# EFM32_IO.net
KiCad netlist of a schematic drawn in Altium Designer
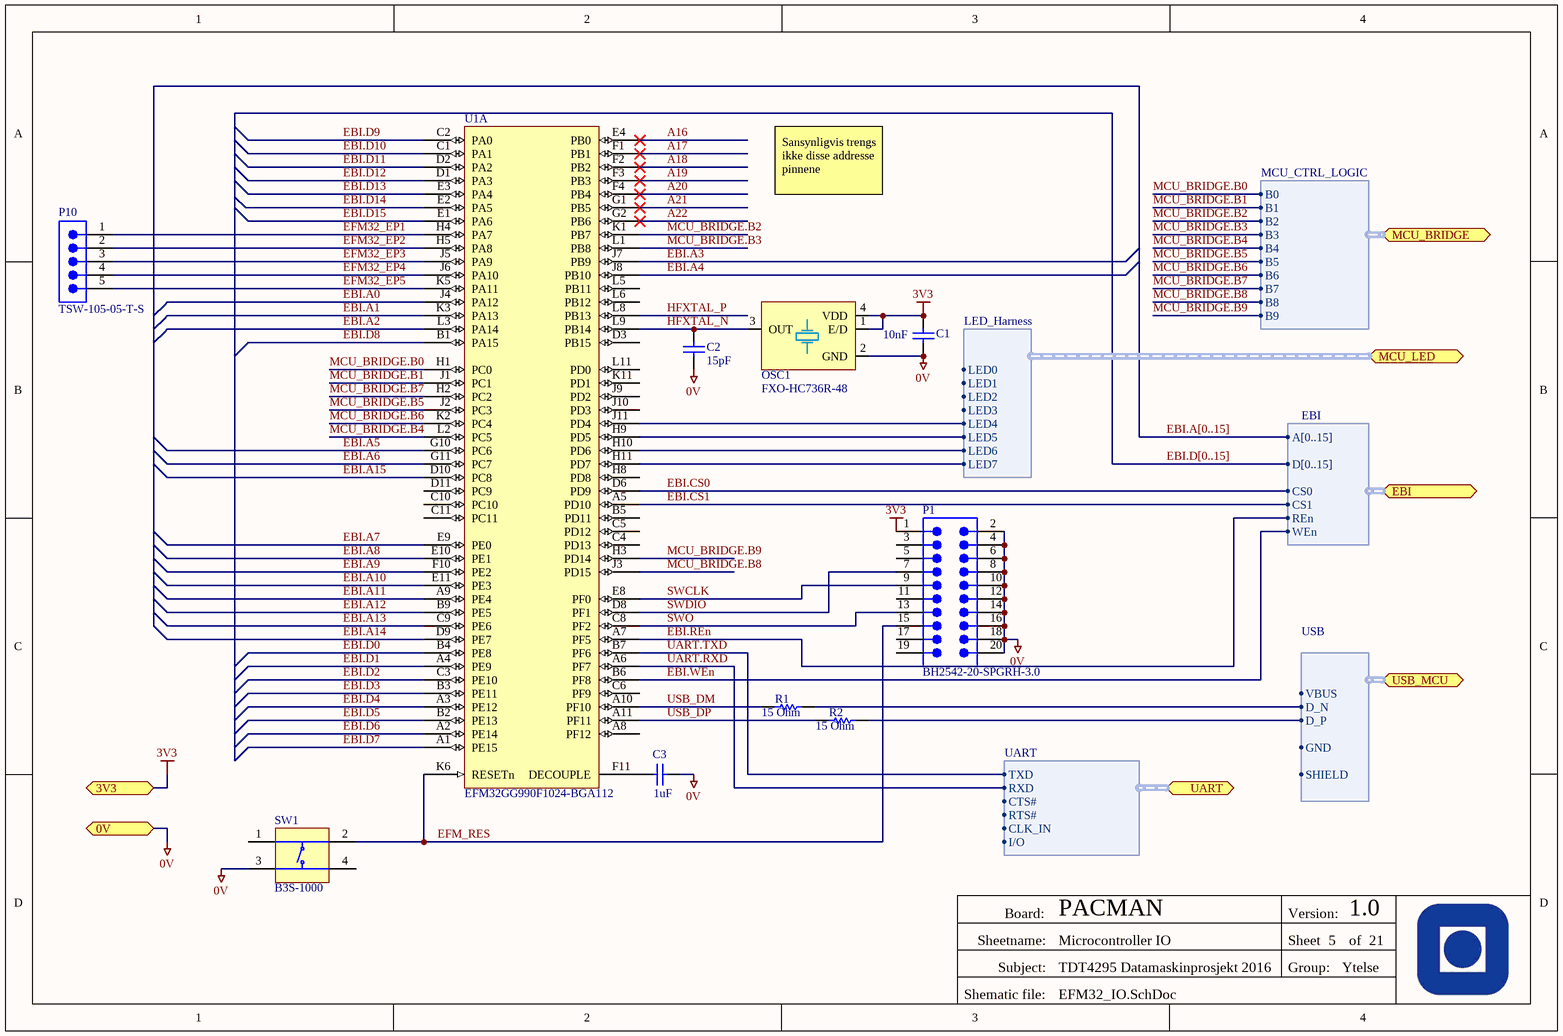
[diagram p0: EFM32_IO.SchDoc]

(export (version "E")
  (design (tool "Eeschema 10.0.6"))
  (components
    (comp (ref "C1")
      (value "10nF")
      (footprint "CAPC0603(1608)100_L")
      (description "CAP 10nF 16V ±1% 0603 (1608 Metric) Thickness 1mm SMD")
      (fields (field (name "TOLERANCE") "Â±1%") (field (name "Comment") "CAP 10nF 16V 0603(1608)"))
      (libsource (lib "Altium Content Vault") (part "CMP-1035-02309-1"))
    )
    (comp (ref "C2")
      (value "15pF")
      (footprint "CAPC0603(1608)100_N")
      (description "CAP 15pF 16V ±0.25pF 0603 (1608 Metric) Thickness 1mm SMD")
      (fields (field (name "TOLERANCE") "Â±0.25pF") (field (name "Comment") "CAP 15pF 16V 0603(1608)"))
      (libsource (lib "Altium Content Vault") (part "CMP-1035-00665-1"))
    )
    (comp (ref "C3")
      (value "1uF")
      (footprint "CAPC0603(1608)100_M")
      (description "CAP 1uF 16V ±10% 0603 (1608 Metric) Thickness 1mm SMD")
      (fields (field (name "TOLERANCE") "Â±10%") (field (name "Comment") "CAP 1uF 16V 0603(1608)"))
      (libsource (lib "Altium Content Vault") (part "CMP-1035-02737-1"))
    )
    (comp (ref "OSC1")
      (value "FXO-HC736R-48")
      (footprint "FXO-HC73")
      (libsource (lib "dmpro16lib") (part "FXO-HC736R-48"))
    )
    (comp (ref "P1")
      (value "BH2542-20-SPGRH-3.0")
      (footprint "PCE-BH2542-20-SPGRH-3.0")
      (description "Box Header, Pitch 2.54 mm, 2x10 Position, Height 9 mm, Tail Length 3 mm")
      (fields (field (name "MANUFACTURER") "Pinchao Electronic"))
      (libsource (lib "Altium Content Vault") (part "CMP-0605-00003-2"))
    )
    (comp (ref "P10")
      (value "TSW-105-05-T-S")
      (footprint "SMTC-TSW-105-05-X-S")
      (description "0.025\" SQ Post Header, Through-hole, Vertical, -55 to 105 degC, 2.54 mm Pitch, 5-Pin, Male, RoHS")
      (fields (field (name "MANUFACTURER") "Samtec"))
      (libsource (lib "Altium Content Vault") (part "SMTC-TSW-105-05-X-S"))
    )
    (comp (ref "R1")
      (value "15 Ohm")
      (footprint "RESC0603(1608)_L")
      (description "15R 0.1W 5% 0603 (1608 Metric)  SMD")
      (fields (field (name "TOLERANCE") "5 %") (field (name "POWER") "0.1 W"))
      (libsource (lib "Altium Content Vault") (part "CMP-1012-00030-1"))
    )
    (comp (ref "R2")
      (value "15 Ohm")
      (footprint "RESC0603(1608)_L")
      (description "15R 0.1W 5% 0603 (1608 Metric)  SMD")
      (fields (field (name "TOLERANCE") "5 %") (field (name "POWER") "0.1 W"))
      (libsource (lib "Altium Content Vault") (part "CMP-1012-00030-1"))
    )
    (comp (ref "SW1")
      (value "B3S-1000")
      (footprint "OMRON-B3S-1000-4_V")
      (description "Sealed Tactile Switch, SPST-NO, 3 to 24 V, -25 to 70 degC, 4-Pin SMD, RoHS, Bulk")
      (libsource (lib "Altium Content Vault") (part "SW-SPST-4_A"))
    )
    (comp (ref "U1")
      (value "EFM32GG990F1024-BGA112")
      (footprint "ENMR-BGA112")
      (fields (field (name "GENERIC PART NUMBER") "EFM32GG990"))
      (libsource (lib "Altium Content Vault") (part "ENMR-EFM32GG990-BGA112"))
    )
  )
  (nets
    (net (code "6") (name "/A16") (class "Default")
      (node (ref "U1") (pin "E4") (pinfunction "PB0_E4") (pintype "bidirectional+no_connect"))
    )
    (net (code "7") (name "/A17") (class "Default")
      (node (ref "U1") (pin "F1") (pinfunction "PB1_F1") (pintype "bidirectional+no_connect"))
    )
    (net (code "8") (name "/A18") (class "Default")
      (node (ref "U1") (pin "F2") (pinfunction "PB2_F2") (pintype "bidirectional+no_connect"))
    )
    (net (code "9") (name "/A19") (class "Default")
      (node (ref "U1") (pin "F3") (pinfunction "PB3_F3") (pintype "bidirectional+no_connect"))
    )
    (net (code "10") (name "/A20") (class "Default")
      (node (ref "U1") (pin "F4") (pinfunction "PB4_F4") (pintype "bidirectional+no_connect"))
    )
    (net (code "11") (name "/A21") (class "Default")
      (node (ref "U1") (pin "G1") (pinfunction "PB5_G1") (pintype "bidirectional+no_connect"))
    )
    (net (code "12") (name "/A22") (class "Default")
      (node (ref "U1") (pin "G2") (pinfunction "PB6_G2") (pintype "bidirectional+no_connect"))
    )
    (net (code "13") (name "/D_N") (class "Default")
      (node (ref "R1") (pin "2") (pinfunction "2_2") (pintype "passive"))
    )
    (net (code "14") (name "/D_P") (class "Default")
      (node (ref "R2") (pin "2") (pinfunction "2_2") (pintype "passive"))
    )
    (net (code "15") (name "/EBI.A0") (class "Default")
      (node (ref "U1") (pin "J4") (pinfunction "PA12_J4") (pintype "bidirectional"))
    )
    (net (code "16") (name "/EBI.A1") (class "Default")
      (node (ref "U1") (pin "K3") (pinfunction "PA13_K3") (pintype "bidirectional"))
    )
    (net (code "17") (name "/EBI.A2") (class "Default")
      (node (ref "U1") (pin "L3") (pinfunction "PA14_L3") (pintype "bidirectional"))
    )
    (net (code "18") (name "/EBI.A3") (class "Default")
      (node (ref "U1") (pin "J7") (pinfunction "PB9_J7") (pintype "bidirectional"))
    )
    (net (code "19") (name "/EBI.A4") (class "Default")
      (node (ref "U1") (pin "J8") (pinfunction "PB10_J8") (pintype "bidirectional"))
    )
    (net (code "20") (name "/EBI.A5") (class "Default")
      (node (ref "U1") (pin "G10") (pinfunction "PC6_G10") (pintype "bidirectional"))
    )
    (net (code "21") (name "/EBI.A6") (class "Default")
      (node (ref "U1") (pin "G11") (pinfunction "PC7_G11") (pintype "bidirectional"))
    )
    (net (code "22") (name "/EBI.A7") (class "Default")
      (node (ref "U1") (pin "E9") (pinfunction "PE0_E9") (pintype "bidirectional"))
    )
    (net (code "23") (name "/EBI.A8") (class "Default")
      (node (ref "U1") (pin "E10") (pinfunction "PE1_E10") (pintype "bidirectional"))
    )
    (net (code "24") (name "/EBI.A9") (class "Default")
      (node (ref "U1") (pin "F10") (pinfunction "PE2_F10") (pintype "bidirectional"))
    )
    (net (code "25") (name "/EBI.A10") (class "Default")
      (node (ref "U1") (pin "E11") (pinfunction "PE3_E11") (pintype "bidirectional"))
    )
    (net (code "26") (name "/EBI.A11") (class "Default")
      (node (ref "U1") (pin "A9") (pinfunction "PE4_A9") (pintype "bidirectional"))
    )
    (net (code "27") (name "/EBI.A12") (class "Default")
      (node (ref "U1") (pin "B9") (pinfunction "PE5_B9") (pintype "bidirectional"))
    )
    (net (code "28") (name "/EBI.A13") (class "Default")
      (node (ref "U1") (pin "C9") (pinfunction "PE6_C9") (pintype "bidirectional"))
    )
    (net (code "29") (name "/EBI.A14") (class "Default")
      (node (ref "U1") (pin "D9") (pinfunction "PE7_D9") (pintype "bidirectional"))
    )
    (net (code "30") (name "/EBI.A15") (class "Default")
      (node (ref "U1") (pin "D10") (pinfunction "PC8_D10") (pintype "bidirectional"))
    )
    (net (code "32") (name "/EBI.CS0") (class "Default")
      (node (ref "U1") (pin "D6") (pinfunction "PD9_D6") (pintype "bidirectional"))
    )
    (net (code "33") (name "/EBI.CS1") (class "Default")
      (node (ref "U1") (pin "A5") (pinfunction "PD10_A5") (pintype "bidirectional"))
    )
    (net (code "34") (name "/EBI.D0") (class "Default")
      (node (ref "U1") (pin "B4") (pinfunction "PE8_B4") (pintype "bidirectional"))
    )
    (net (code "35") (name "/EBI.D1") (class "Default")
      (node (ref "U1") (pin "A4") (pinfunction "PE9_A4") (pintype "bidirectional"))
    )
    (net (code "36") (name "/EBI.D2") (class "Default")
      (node (ref "U1") (pin "C3") (pinfunction "PE10_C3") (pintype "bidirectional"))
    )
    (net (code "37") (name "/EBI.D3") (class "Default")
      (node (ref "U1") (pin "B3") (pinfunction "PE11_B3") (pintype "bidirectional"))
    )
    (net (code "38") (name "/EBI.D4") (class "Default")
      (node (ref "U1") (pin "A3") (pinfunction "PE12_A3") (pintype "bidirectional"))
    )
    (net (code "39") (name "/EBI.D5") (class "Default")
      (node (ref "U1") (pin "B2") (pinfunction "PE13_B2") (pintype "bidirectional"))
    )
    (net (code "40") (name "/EBI.D6") (class "Default")
      (node (ref "U1") (pin "A2") (pinfunction "PE14_A2") (pintype "bidirectional"))
    )
    (net (code "41") (name "/EBI.D7") (class "Default")
      (node (ref "U1") (pin "A1") (pinfunction "PE15_A1") (pintype "bidirectional"))
    )
    (net (code "42") (name "/EBI.D8") (class "Default")
      (node (ref "U1") (pin "B1") (pinfunction "PA15_B1") (pintype "bidirectional"))
    )
    (net (code "43") (name "/EBI.D9") (class "Default")
      (node (ref "U1") (pin "C2") (pinfunction "PA0_C2") (pintype "bidirectional"))
    )
    (net (code "44") (name "/EBI.D10") (class "Default")
      (node (ref "U1") (pin "C1") (pinfunction "PA1_C1") (pintype "bidirectional"))
    )
    (net (code "45") (name "/EBI.D11") (class "Default")
      (node (ref "U1") (pin "D2") (pinfunction "PA2_D2") (pintype "bidirectional"))
    )
    (net (code "46") (name "/EBI.D12") (class "Default")
      (node (ref "U1") (pin "D1") (pinfunction "PA3_D1") (pintype "bidirectional"))
    )
    (net (code "47") (name "/EBI.D13") (class "Default")
      (node (ref "U1") (pin "E3") (pinfunction "PA4_E3") (pintype "bidirectional"))
    )
    (net (code "48") (name "/EBI.D14") (class "Default")
      (node (ref "U1") (pin "E2") (pinfunction "PA5_E2") (pintype "bidirectional"))
    )
    (net (code "49") (name "/EBI.D15") (class "Default")
      (node (ref "U1") (pin "E1") (pinfunction "PA6_E1") (pintype "bidirectional"))
    )
    (net (code "51") (name "/EBI.REn") (class "Default")
      (node (ref "U1") (pin "A7") (pinfunction "PF5_A7") (pintype "bidirectional"))
    )
    (net (code "52") (name "/EBI.WEn") (class "Default")
      (node (ref "U1") (pin "B6") (pinfunction "PF8_B6") (pintype "bidirectional"))
    )
    (net (code "53") (name "/EFM32_EP1") (class "Default")
      (node (ref "P10") (pin "1") (pinfunction "1_1") (pintype "passive"))
      (node (ref "U1") (pin "H4") (pinfunction "PA7_H4") (pintype "bidirectional"))
    )
    (net (code "54") (name "/EFM32_EP2") (class "Default")
      (node (ref "P10") (pin "2") (pinfunction "2_2") (pintype "passive"))
      (node (ref "U1") (pin "H5") (pinfunction "PA8_H5") (pintype "bidirectional"))
    )
    (net (code "55") (name "/EFM32_EP3") (class "Default")
      (node (ref "P10") (pin "3") (pinfunction "3_3") (pintype "passive"))
      (node (ref "U1") (pin "J5") (pinfunction "PA9_J5") (pintype "bidirectional"))
    )
    (net (code "56") (name "/EFM32_EP4") (class "Default")
      (node (ref "P10") (pin "4") (pinfunction "4_4") (pintype "passive"))
      (node (ref "U1") (pin "J6") (pinfunction "PA10_J6") (pintype "bidirectional"))
    )
    (net (code "57") (name "/EFM32_EP5") (class "Default")
      (node (ref "P10") (pin "5") (pinfunction "5_5") (pintype "passive"))
      (node (ref "U1") (pin "K5") (pinfunction "PA11_K5") (pintype "bidirectional"))
    )
    (net (code "58") (name "/EFM_RES") (class "Default")
      (node (ref "P1") (pin "15") (pinfunction "15_15") (pintype "passive"))
      (node (ref "SW1") (pin "2") (pinfunction "2_2") (pintype "passive"))
      (node (ref "U1") (pin "K6") (pinfunction "RESETn_K6") (pintype "input"))
    )
    (net (code "59") (name "/HFXTAL_N") (class "Default")
      (node (ref "C2") (pin "2") (pinfunction "2_2") (pintype "passive"))
      (node (ref "OSC1") (pin "3") (pinfunction "OUT_3") (pintype "passive"))
      (node (ref "U1") (pin "L9") (pinfunction "PB14_L9") (pintype "bidirectional"))
    )
    (net (code "60") (name "/HFXTAL_P") (class "Default")
      (node (ref "U1") (pin "L8") (pinfunction "PB13_L8") (pintype "bidirectional"))
    )
    (net (code "61") (name "/LED4") (class "Default")
      (node (ref "U1") (pin "J11") (pinfunction "PD4_J11") (pintype "bidirectional"))
    )
    (net (code "62") (name "/LED5") (class "Default")
      (node (ref "U1") (pin "H9") (pinfunction "PD5_H9") (pintype "bidirectional"))
    )
    (net (code "63") (name "/LED6") (class "Default")
      (node (ref "U1") (pin "H10") (pinfunction "PD6_H10") (pintype "bidirectional"))
    )
    (net (code "64") (name "/LED7") (class "Default")
      (node (ref "U1") (pin "H11") (pinfunction "PD7_H11") (pintype "bidirectional"))
    )
    (net (code "65") (name "/MCU_BRIDGE.B0") (class "Default")
      (node (ref "U1") (pin "H1") (pinfunction "PC0_H1") (pintype "bidirectional"))
    )
    (net (code "66") (name "/MCU_BRIDGE.B1") (class "Default")
      (node (ref "U1") (pin "J1") (pinfunction "PC1_J1") (pintype "bidirectional"))
    )
    (net (code "67") (name "/MCU_BRIDGE.B2") (class "Default")
      (node (ref "U1") (pin "K1") (pinfunction "PB7_K1") (pintype "bidirectional"))
    )
    (net (code "68") (name "/MCU_BRIDGE.B3") (class "Default")
      (node (ref "U1") (pin "L1") (pinfunction "PB8_L1") (pintype "bidirectional"))
    )
    (net (code "69") (name "/MCU_BRIDGE.B4") (class "Default")
      (node (ref "U1") (pin "L2") (pinfunction "PC5_L2") (pintype "bidirectional"))
    )
    (net (code "70") (name "/MCU_BRIDGE.B5") (class "Default")
      (node (ref "U1") (pin "J2") (pinfunction "PC3_J2") (pintype "bidirectional"))
    )
    (net (code "71") (name "/MCU_BRIDGE.B6") (class "Default")
      (node (ref "U1") (pin "K2") (pinfunction "PC4_K2") (pintype "bidirectional"))
    )
    (net (code "72") (name "/MCU_BRIDGE.B7") (class "Default")
      (node (ref "U1") (pin "H2") (pinfunction "PC2_H2") (pintype "bidirectional"))
    )
    (net (code "73") (name "/MCU_BRIDGE.B8") (class "Default")
      (node (ref "U1") (pin "J3") (pinfunction "PD15_J3") (pintype "bidirectional"))
    )
    (net (code "74") (name "/MCU_BRIDGE.B9") (class "Default")
      (node (ref "U1") (pin "H3") (pinfunction "PD14_H3") (pintype "bidirectional"))
    )
    (net (code "75") (name "/SWCLK") (class "Default")
      (node (ref "P1") (pin "9") (pinfunction "9_9") (pintype "passive"))
      (node (ref "U1") (pin "E8") (pinfunction "PF0_E8") (pintype "bidirectional"))
    )
    (net (code "76") (name "/SWDIO") (class "Default")
      (node (ref "P1") (pin "7") (pinfunction "7_7") (pintype "passive"))
      (node (ref "U1") (pin "D8") (pinfunction "PF1_D8") (pintype "bidirectional"))
    )
    (net (code "77") (name "/SWO") (class "Default")
      (node (ref "P1") (pin "13") (pinfunction "13_13") (pintype "passive"))
      (node (ref "U1") (pin "C8") (pinfunction "PF2_C8") (pintype "bidirectional"))
    )
    (net (code "78") (name "/UART.RXD") (class "Default")
      (node (ref "U1") (pin "A6") (pinfunction "PF7_A6") (pintype "bidirectional"))
    )
    (net (code "79") (name "/UART.TXD") (class "Default")
      (node (ref "U1") (pin "B7") (pinfunction "PF6_B7") (pintype "bidirectional"))
    )
    (net (code "80") (name "/USB_DM") (class "Default")
      (node (ref "R1") (pin "1") (pinfunction "1_1") (pintype "passive"))
      (node (ref "U1") (pin "A10") (pinfunction "PF10_A10") (pintype "bidirectional"))
    )
    (net (code "81") (name "/USB_DP") (class "Default")
      (node (ref "R2") (pin "1") (pinfunction "1_1") (pintype "passive"))
      (node (ref "U1") (pin "A11") (pinfunction "PF11_A11") (pintype "bidirectional"))
    )
    (net (code "87") (name "0V") (class "Default")
      (node (ref "C1") (pin "1") (pinfunction "1_1") (pintype "passive"))
      (node (ref "C2") (pin "1") (pinfunction "1_1") (pintype "passive"))
      (node (ref "C3") (pin "2") (pinfunction "2_2") (pintype "passive"))
      (node (ref "OSC1") (pin "2") (pinfunction "GND_2") (pintype "passive"))
      (node (ref "P1") (pin "10") (pinfunction "10_10") (pintype "passive"))
      (node (ref "P1") (pin "12") (pinfunction "12_12") (pintype "passive"))
      (node (ref "P1") (pin "14") (pinfunction "14_14") (pintype "passive"))
      (node (ref "P1") (pin "16") (pinfunction "16_16") (pintype "passive"))
      (node (ref "P1") (pin "18") (pinfunction "18_18") (pintype "passive"))
      (node (ref "P1") (pin "2") (pinfunction "2_2") (pintype "passive"))
      (node (ref "P1") (pin "20") (pinfunction "20_20") (pintype "passive"))
      (node (ref "P1") (pin "4") (pinfunction "4_4") (pintype "passive"))
      (node (ref "P1") (pin "6") (pinfunction "6_6") (pintype "passive"))
      (node (ref "P1") (pin "8") (pinfunction "8_8") (pintype "passive"))
      (node (ref "SW1") (pin "3") (pinfunction "3_3") (pintype "passive"))
    )
    (net (code "88") (name "3V3") (class "Default")
      (node (ref "C1") (pin "2") (pinfunction "2_2") (pintype "passive"))
      (node (ref "OSC1") (pin "1") (pinfunction "E/D_1") (pintype "passive"))
      (node (ref "OSC1") (pin "4") (pinfunction "VDD_4") (pintype "passive"))
      (node (ref "P1") (pin "1") (pinfunction "1_1") (pintype "passive"))
    )
    (net (code "89") (name "Net-(U1A-DECOUPLE)") (class "Default")
      (node (ref "C3") (pin "1") (pinfunction "1_1") (pintype "passive"))
      (node (ref "U1") (pin "F11") (pinfunction "DECOUPLE_F11") (pintype "passive"))
    )
    (net (code "90") (name "unconnected-(P1-Pad3)") (class "Default")
      (node (ref "P1") (pin "3") (pinfunction "3_3") (pintype "passive"))
    )
    (net (code "91") (name "unconnected-(P1-Pad5)") (class "Default")
      (node (ref "P1") (pin "5") (pinfunction "5_5") (pintype "passive"))
    )
    (net (code "92") (name "unconnected-(P1-Pad11)") (class "Default")
      (node (ref "P1") (pin "11") (pinfunction "11_11") (pintype "passive"))
    )
    (net (code "93") (name "unconnected-(P1-Pad17)") (class "Default")
      (node (ref "P1") (pin "17") (pinfunction "17_17") (pintype "passive"))
    )
    (net (code "94") (name "unconnected-(P1-Pad19)") (class "Default")
      (node (ref "P1") (pin "19") (pinfunction "19_19") (pintype "passive"))
    )
    (net (code "95") (name "unconnected-(SW1-Pad1)") (class "Default")
      (node (ref "SW1") (pin "1") (pinfunction "1_1") (pintype "passive"))
    )
    (net (code "96") (name "unconnected-(SW1-Pad4)") (class "Default")
      (node (ref "SW1") (pin "4") (pinfunction "4_4") (pintype "passive"))
    )
    (net (code "97") (name "unconnected-(U1A-PB11-PadL5)") (class "Default")
      (node (ref "U1") (pin "L5") (pinfunction "PB11_L5") (pintype "bidirectional"))
    )
    (net (code "98") (name "unconnected-(U1A-PB12-PadL6)") (class "Default")
      (node (ref "U1") (pin "L6") (pinfunction "PB12_L6") (pintype "bidirectional"))
    )
    (net (code "99") (name "unconnected-(U1A-PB15-PadD3)") (class "Default")
      (node (ref "U1") (pin "D3") (pinfunction "PB15_D3") (pintype "bidirectional"))
    )
    (net (code "100") (name "unconnected-(U1A-PC9-PadD11)") (class "Default")
      (node (ref "U1") (pin "D11") (pinfunction "PC9_D11") (pintype "bidirectional"))
    )
    (net (code "101") (name "unconnected-(U1A-PC10-PadC10)") (class "Default")
      (node (ref "U1") (pin "C10") (pinfunction "PC10_C10") (pintype "bidirectional"))
    )
    (net (code "102") (name "unconnected-(U1A-PC11-PadC11)") (class "Default")
      (node (ref "U1") (pin "C11") (pinfunction "PC11_C11") (pintype "bidirectional"))
    )
    (net (code "103") (name "unconnected-(U1A-PD0-PadL11)") (class "Default")
      (node (ref "U1") (pin "L11") (pinfunction "PD0_L11") (pintype "bidirectional"))
    )
    (net (code "104") (name "unconnected-(U1A-PD1-PadK11)") (class "Default")
      (node (ref "U1") (pin "K11") (pinfunction "PD1_K11") (pintype "bidirectional"))
    )
    (net (code "105") (name "unconnected-(U1A-PD2-PadJ9)") (class "Default")
      (node (ref "U1") (pin "J9") (pinfunction "PD2_J9") (pintype "bidirectional"))
    )
    (net (code "106") (name "unconnected-(U1A-PD3-PadJ10)") (class "Default")
      (node (ref "U1") (pin "J10") (pinfunction "PD3_J10") (pintype "bidirectional"))
    )
    (net (code "107") (name "unconnected-(U1A-PD8-PadH8)") (class "Default")
      (node (ref "U1") (pin "H8") (pinfunction "PD8_H8") (pintype "bidirectional"))
    )
    (net (code "108") (name "unconnected-(U1A-PD11-PadB5)") (class "Default")
      (node (ref "U1") (pin "B5") (pinfunction "PD11_B5") (pintype "bidirectional"))
    )
    (net (code "109") (name "unconnected-(U1A-PD12-PadC5)") (class "Default")
      (node (ref "U1") (pin "C5") (pinfunction "PD12_C5") (pintype "bidirectional"))
    )
    (net (code "110") (name "unconnected-(U1A-PD13-PadC4)") (class "Default")
      (node (ref "U1") (pin "C4") (pinfunction "PD13_C4") (pintype "bidirectional"))
    )
    (net (code "111") (name "unconnected-(U1A-PF9-PadC6)") (class "Default")
      (node (ref "U1") (pin "C6") (pinfunction "PF9_C6") (pintype "bidirectional"))
    )
    (net (code "112") (name "unconnected-(U1A-PF12-PadA8)") (class "Default")
      (node (ref "U1") (pin "A8") (pinfunction "PF12_A8") (pintype "bidirectional"))
    )
  )
)
